# ledstringpower2.net
KiCad netlist of a schematic drawn in EAGLE
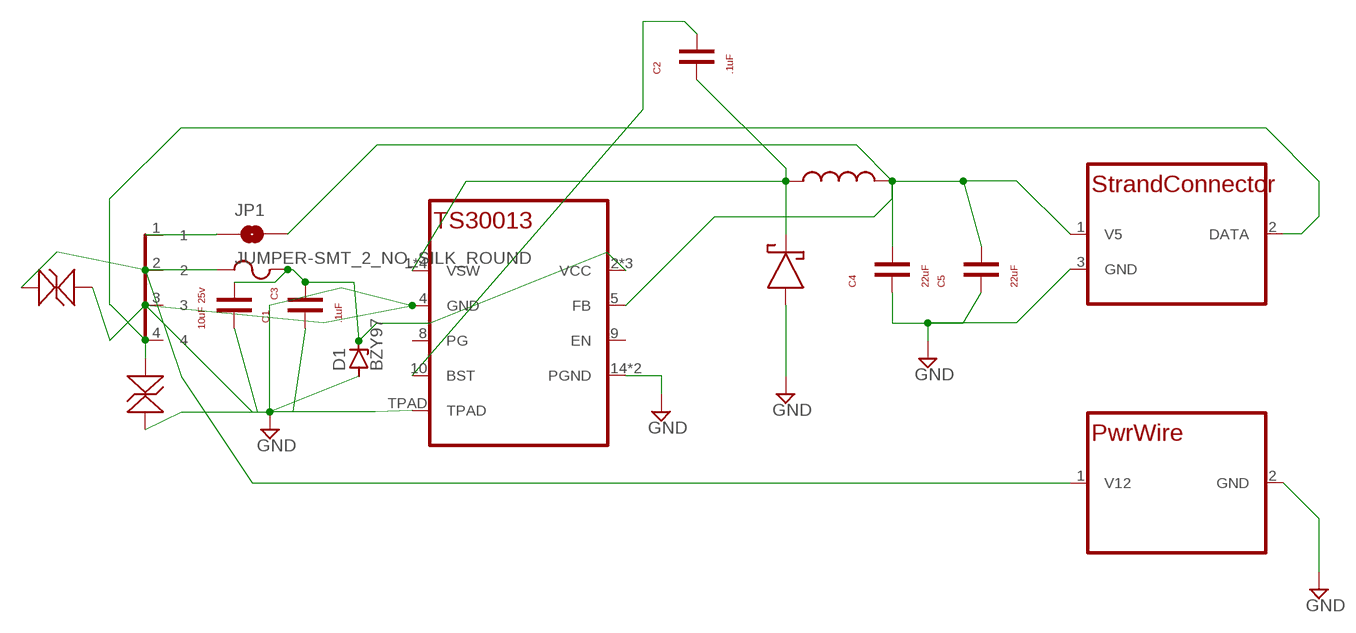
[diagram p0: schematic, sheet 1]

(export (version "E")
  (design (tool "Eeschema 10.0.6"))
  (components
    (comp (ref "C1")
      (value ".1uF")
      (footprint "eagle-import:C0603")
      (libsource (lib "eagle-import") (part "CAPACITOR_NONPOLARC0603"))
    )
    (comp (ref "C2")
      (value ".1uF")
      (footprint "eagle-import:C0603")
      (libsource (lib "eagle-import") (part "CAPACITOR_NONPOLARC0603"))
    )
    (comp (ref "C3")
      (value "10uF 25v")
      (footprint "eagle-import:C1206")
      (libsource (lib "eagle-import") (part "CL31A106MAHNNNEC1206"))
    )
    (comp (ref "C4")
      (value "22uF")
      (footprint "eagle-import:C0603")
      (libsource (lib "eagle-import") (part "GRM188R61A226ME15DC0603"))
    )
    (comp (ref "C5")
      (value "22uF")
      (footprint "eagle-import:C0603")
      (libsource (lib "eagle-import") (part "GRM188R61A226ME15DC0603"))
    )
    (comp (ref "D1")
      (value "BZY97")
      (footprint "eagle-import:F126Z12")
      (libsource (lib "eagle-import") (part "BZY97"))
    )
    (comp (ref "D2")
      (value "LS54LS54")
      (footprint "eagle-import:LS54")
      (libsource (lib "eagle-import") (part "LS54LS54"))
    )
    (comp (ref "F1")
      (value "3A")
      (footprint "eagle-import:R0603")
      (libsource (lib "eagle-import") (part "FUSER0603"))
    )
    (comp (ref "IC1")
      (value "TS30013QFN16")
      (footprint "eagle-import:QFN16")
      (libsource (lib "eagle-import") (part "TS30013QFN16"))
    )
    (comp (ref "JP1")
      (value "JUMPER-SMT_2_NO_SILK_ROUND")
      (footprint "eagle-import:SMT-JUMPER_2_NO_SILK_ROUND")
      (libsource (lib "eagle-import") (part "JUMPER-SMT_2_NO_SILK_ROUND"))
    )
    (comp (ref "L1")
      (value "SRN5040TA-4R7MSRN5040TA")
      (footprint "eagle-import:SRN5040TA")
      (libsource (lib "eagle-import") (part "SRN5040TA-4R7MSRN5040TA"))
    )
    (comp (ref "TVS1")
      (value "DESD5V0U1BL-7BDFN1006-2")
      (footprint "eagle-import:DFN1006-2")
      (libsource (lib "eagle-import") (part "DESD5V0U1BL-7BDFN1006-2"))
    )
    (comp (ref "TVS2")
      (value "DESD5V0U1BL-7BDFN1006-2")
      (footprint "eagle-import:DFN1006-2")
      (libsource (lib "eagle-import") (part "DESD5V0U1BL-7BDFN1006-2"))
    )
    (comp (ref "U$3")
      (value "TE-1969806-1TE-1969806-1")
      (footprint "eagle-import:TE-1969806-1")
      (libsource (lib "eagle-import") (part "TE-1969806-1TE-1969806-1"))
    )
    (comp (ref "U$5")
      (value "LEDSTRANDDLEDWIREP")
      (footprint "eagle-import:LEDWIREP")
      (libsource (lib "eagle-import") (part "LEDSTRANDDLEDWIREP"))
    )
    (comp (ref "U$8")
      (value "PWRWIREDPWRWIREP")
      (footprint "eagle-import:PWRWIREP")
      (libsource (lib "eagle-import") (part "PWRWIREDPWRWIREP"))
    )
  )
  (nets
    (net (code "1") (name "GND") (class "Default")
      (node (ref "C1") (pin "1") (pinfunction "1_1") (pintype "bidirectional"))
      (node (ref "C3") (pin "2") (pinfunction "2_2") (pintype "bidirectional"))
      (node (ref "C4") (pin "1") (pinfunction "1_1") (pintype "bidirectional"))
      (node (ref "C5") (pin "1") (pinfunction "1_1") (pintype "bidirectional"))
      (node (ref "D1") (pin "A") (pinfunction "A_A") (pintype "passive"))
      (node (ref "D2") (pin "1") (pinfunction "1_1") (pintype "bidirectional"))
      (node (ref "IC1") (pin "14") (pinfunction "PGND_14") (pintype "bidirectional"))
      (node (ref "IC1") (pin "15") (pinfunction "PGND_15") (pintype "bidirectional"))
      (node (ref "IC1") (pin "4") (pinfunction "GND_4") (pintype "bidirectional"))
      (node (ref "IC1") (pin "TPAD") (pinfunction "TPAD_TPAD") (pintype "bidirectional"))
      (node (ref "TVS1") (pin "1") (pinfunction "1_1") (pintype "bidirectional"))
      (node (ref "TVS2") (pin "1") (pinfunction "1_1") (pintype "bidirectional"))
      (node (ref "U$3") (pin "3") (pinfunction "3_3") (pintype "bidirectional"))
      (node (ref "U$5") (pin "3") (pinfunction "GND_3") (pintype "bidirectional"))
      (node (ref "U$8") (pin "2") (pinfunction "GND_2") (pintype "bidirectional"))
    )
    (net (code "2") (name "Net-(C1-Pad2)") (class "Default")
      (node (ref "C1") (pin "2") (pinfunction "2_2") (pintype "bidirectional"))
      (node (ref "C3") (pin "1") (pinfunction "1_1") (pintype "bidirectional"))
      (node (ref "D1") (pin "C") (pinfunction "C_C") (pintype "passive"))
      (node (ref "F1") (pin "2") (pinfunction "2_2") (pintype "bidirectional"))
      (node (ref "IC1") (pin "11") (pinfunction "VCC_11") (pintype "bidirectional"))
      (node (ref "IC1") (pin "2") (pinfunction "VCC_2") (pintype "bidirectional"))
      (node (ref "IC1") (pin "3") (pinfunction "VCC_3") (pintype "bidirectional"))
    )
    (net (code "3") (name "Net-(C2-Pad1)") (class "Default")
      (node (ref "C2") (pin "1") (pinfunction "1_1") (pintype "bidirectional"))
      (node (ref "D2") (pin "2") (pinfunction "2_2") (pintype "bidirectional"))
      (node (ref "IC1") (pin "1") (pinfunction "VSW_1") (pintype "bidirectional"))
      (node (ref "IC1") (pin "12") (pinfunction "VSW_12") (pintype "bidirectional"))
      (node (ref "IC1") (pin "13") (pinfunction "VSW_13") (pintype "bidirectional"))
      (node (ref "IC1") (pin "16") (pinfunction "VSW_16") (pintype "bidirectional"))
      (node (ref "L1") (pin "1") (pinfunction "1_1") (pintype "bidirectional"))
    )
    (net (code "4") (name "Net-(IC1-BST)") (class "Default")
      (node (ref "C2") (pin "2") (pinfunction "2_2") (pintype "bidirectional"))
      (node (ref "IC1") (pin "10") (pinfunction "BST_10") (pintype "bidirectional"))
    )
    (net (code "5") (name "Net-(IC1-FB)") (class "Default")
      (node (ref "C4") (pin "2") (pinfunction "2_2") (pintype "bidirectional"))
      (node (ref "C5") (pin "2") (pinfunction "2_2") (pintype "bidirectional"))
      (node (ref "IC1") (pin "5") (pinfunction "FB_5") (pintype "bidirectional"))
      (node (ref "JP1") (pin "2") (pinfunction "2_2") (pintype "passive"))
      (node (ref "L1") (pin "2") (pinfunction "2_2") (pintype "bidirectional"))
      (node (ref "U$5") (pin "1") (pinfunction "V5_1") (pintype "bidirectional"))
    )
    (net (code "6") (name "Net-(JP1-Pad1)") (class "Default")
      (node (ref "JP1") (pin "1") (pinfunction "1_1") (pintype "passive"))
      (node (ref "U$3") (pin "1") (pinfunction "1_1") (pintype "bidirectional"))
    )
    (net (code "7") (name "Net-(U$5-DATA)") (class "Default")
      (node (ref "TVS2") (pin "2") (pinfunction "2_2") (pintype "bidirectional"))
      (node (ref "U$3") (pin "4") (pinfunction "4_4") (pintype "bidirectional"))
      (node (ref "U$5") (pin "2") (pinfunction "DATA_2") (pintype "bidirectional"))
    )
    (net (code "8") (name "Net-(U$8-V12)") (class "Default")
      (node (ref "F1") (pin "1") (pinfunction "1_1") (pintype "bidirectional"))
      (node (ref "TVS1") (pin "2") (pinfunction "2_2") (pintype "bidirectional"))
      (node (ref "U$3") (pin "2") (pinfunction "2_2") (pintype "bidirectional"))
      (node (ref "U$8") (pin "1") (pinfunction "V12_1") (pintype "bidirectional"))
    )
    (net (code "9") (name "unconnected-(IC1-EN-Pad9)") (class "Default")
      (node (ref "IC1") (pin "9") (pinfunction "EN_9") (pintype "bidirectional"))
    )
    (net (code "10") (name "unconnected-(IC1-PG-Pad8)") (class "Default")
      (node (ref "IC1") (pin "8") (pinfunction "PG_8") (pintype "bidirectional"))
    )
  )
)
